# battery_cell.net
KiCad netlist of a schematic drawn in Altium Designer
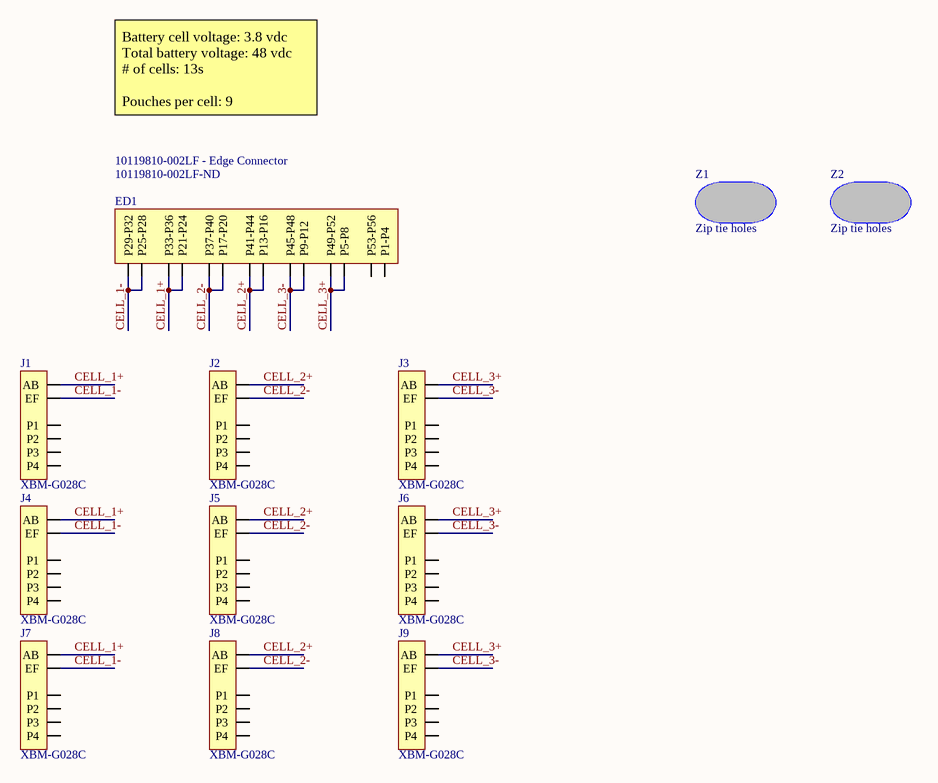
[diagram p0: battery_cell.SchDoc]

(export (version "E")
  (design (tool "Eeschema 10.0.6"))
  (components
    (comp (ref "ED1")
      (value "10119810-002LF - Edge Connector")
      (footprint "10119810-002LF - Edge Connector")
      (fields (field (name "SUPPLIER PART NUMBER 1") "10119810-002LF-ND"))
      (libsource (lib "bms") (part "10119810-002LF - Edge Connector"))
    )
    (comp (ref "J1")
      (value "XBM-G028C")
      (footprint "XBM-G028A")
      (description "28 pos power connector  (0.8X1.6mm pitch)-with post")
      (fields (field (name "MANUFACTURER") "Neoconix"))
      (libsource (lib "bms") (part "XBM-G028C"))
    )
    (comp (ref "J2")
      (value "XBM-G028C")
      (footprint "XBM-G028A")
      (description "28 pos power connector  (0.8X1.6mm pitch)-with post")
      (fields (field (name "MANUFACTURER") "Neoconix"))
      (libsource (lib "bms") (part "XBM-G028C"))
    )
    (comp (ref "J3")
      (value "XBM-G028C")
      (footprint "XBM-G028A")
      (description "28 pos power connector  (0.8X1.6mm pitch)-with post")
      (fields (field (name "MANUFACTURER") "Neoconix"))
      (libsource (lib "bms") (part "XBM-G028C"))
    )
    (comp (ref "J4")
      (value "XBM-G028C")
      (footprint "XBM-G028A")
      (description "28 pos power connector  (0.8X1.6mm pitch)-with post")
      (fields (field (name "MANUFACTURER") "Neoconix"))
      (libsource (lib "bms") (part "XBM-G028C"))
    )
    (comp (ref "J5")
      (value "XBM-G028C")
      (footprint "XBM-G028A")
      (description "28 pos power connector  (0.8X1.6mm pitch)-with post")
      (fields (field (name "MANUFACTURER") "Neoconix"))
      (libsource (lib "bms") (part "XBM-G028C"))
    )
    (comp (ref "J6")
      (value "XBM-G028C")
      (footprint "XBM-G028A")
      (description "28 pos power connector  (0.8X1.6mm pitch)-with post")
      (fields (field (name "MANUFACTURER") "Neoconix"))
      (libsource (lib "bms") (part "XBM-G028C"))
    )
    (comp (ref "J7")
      (value "XBM-G028C")
      (footprint "XBM-G028A")
      (description "28 pos power connector  (0.8X1.6mm pitch)-with post")
      (fields (field (name "MANUFACTURER") "Neoconix"))
      (libsource (lib "bms") (part "XBM-G028C"))
    )
    (comp (ref "J8")
      (value "XBM-G028C")
      (footprint "XBM-G028A")
      (description "28 pos power connector  (0.8X1.6mm pitch)-with post")
      (fields (field (name "MANUFACTURER") "Neoconix"))
      (libsource (lib "bms") (part "XBM-G028C"))
    )
    (comp (ref "J9")
      (value "XBM-G028C")
      (footprint "XBM-G028A")
      (description "28 pos power connector  (0.8X1.6mm pitch)-with post")
      (fields (field (name "MANUFACTURER") "Neoconix"))
      (libsource (lib "bms") (part "XBM-G028C"))
    )
    (comp (ref "Z1")
      (value "Zip tie holes")
      (footprint "ZIP_TIE_HOLE")
      (libsource (lib "bms") (part "ZIP_TIE_HOLE"))
    )
    (comp (ref "Z2")
      (value "Zip tie holes")
      (footprint "ZIP_TIE_HOLE")
      (libsource (lib "bms") (part "ZIP_TIE_HOLE"))
    )
  )
  (nets
    (net (code "1") (name "/CELL_1+") (class "Default")
      (node (ref "ED1") (pin "P21-P24") (pinfunction "P21-P24_P21-P24") (pintype "power_in"))
      (node (ref "ED1") (pin "P33-P36") (pinfunction "P33-P36_P33-P36") (pintype "power_in"))
      (node (ref "J1") (pin "AB") (pinfunction "AB_AB") (pintype "power_in"))
      (node (ref "J4") (pin "AB") (pinfunction "AB_AB") (pintype "power_in"))
      (node (ref "J7") (pin "AB") (pinfunction "AB_AB") (pintype "power_in"))
    )
    (net (code "2") (name "/CELL_1-") (class "Default")
      (node (ref "ED1") (pin "P25-P28") (pinfunction "P25-P28_P25-P28") (pintype "power_in"))
      (node (ref "ED1") (pin "P29-P32") (pinfunction "P29-P32_P29-P32") (pintype "power_in"))
      (node (ref "J1") (pin "EF") (pinfunction "EF_EF") (pintype "power_in"))
      (node (ref "J4") (pin "EF") (pinfunction "EF_EF") (pintype "power_in"))
      (node (ref "J7") (pin "EF") (pinfunction "EF_EF") (pintype "power_in"))
    )
    (net (code "3") (name "/CELL_2+") (class "Default")
      (node (ref "ED1") (pin "P13-P16") (pinfunction "P13-P16_P13-P16") (pintype "power_in"))
      (node (ref "ED1") (pin "P41-P44") (pinfunction "P41-P44_P41-P44") (pintype "power_in"))
      (node (ref "J2") (pin "AB") (pinfunction "AB_AB") (pintype "power_in"))
      (node (ref "J5") (pin "AB") (pinfunction "AB_AB") (pintype "power_in"))
      (node (ref "J8") (pin "AB") (pinfunction "AB_AB") (pintype "power_in"))
    )
    (net (code "4") (name "/CELL_2-") (class "Default")
      (node (ref "ED1") (pin "P17-P20") (pinfunction "P17-P20_P17-P20") (pintype "power_in"))
      (node (ref "ED1") (pin "P37-P40") (pinfunction "P37-P40_P37-P40") (pintype "power_in"))
      (node (ref "J2") (pin "EF") (pinfunction "EF_EF") (pintype "power_in"))
      (node (ref "J5") (pin "EF") (pinfunction "EF_EF") (pintype "power_in"))
      (node (ref "J8") (pin "EF") (pinfunction "EF_EF") (pintype "power_in"))
    )
    (net (code "5") (name "/CELL_3+") (class "Default")
      (node (ref "ED1") (pin "P49-P52") (pinfunction "P49-P52_P49-P52") (pintype "power_in"))
      (node (ref "ED1") (pin "P5-P8") (pinfunction "P5-P8_P5-P8") (pintype "power_in"))
      (node (ref "J3") (pin "AB") (pinfunction "AB_AB") (pintype "power_in"))
      (node (ref "J6") (pin "AB") (pinfunction "AB_AB") (pintype "power_in"))
      (node (ref "J9") (pin "AB") (pinfunction "AB_AB") (pintype "power_in"))
    )
    (net (code "6") (name "/CELL_3-") (class "Default")
      (node (ref "ED1") (pin "P45-P48") (pinfunction "P45-P48_P45-P48") (pintype "power_in"))
      (node (ref "ED1") (pin "P9-P12") (pinfunction "P9-P12_P9-P12") (pintype "power_in"))
      (node (ref "J3") (pin "EF") (pinfunction "EF_EF") (pintype "power_in"))
      (node (ref "J6") (pin "EF") (pinfunction "EF_EF") (pintype "power_in"))
      (node (ref "J9") (pin "EF") (pinfunction "EF_EF") (pintype "power_in"))
    )
    (net (code "7") (name "unconnected-(ED1-PadP1-P4)") (class "Default")
      (node (ref "ED1") (pin "P1-P4") (pinfunction "P1-P4_P1-P4") (pintype "power_in"))
    )
    (net (code "8") (name "unconnected-(ED1-PadP53-P56)") (class "Default")
      (node (ref "ED1") (pin "P53-P56") (pinfunction "P53-P56_P53-P56") (pintype "power_in"))
    )
    (net (code "9") (name "unconnected-(J1-PadP1)") (class "Default")
      (node (ref "J1") (pin "P1") (pinfunction "P1_P1") (pintype "passive"))
    )
    (net (code "10") (name "unconnected-(J1-PadP2)") (class "Default")
      (node (ref "J1") (pin "P2") (pinfunction "P2_P2") (pintype "passive"))
    )
    (net (code "11") (name "unconnected-(J1-PadP3)") (class "Default")
      (node (ref "J1") (pin "P3") (pinfunction "P3_P3") (pintype "passive"))
    )
    (net (code "12") (name "unconnected-(J1-PadP4)") (class "Default")
      (node (ref "J1") (pin "P4") (pinfunction "P4_P4") (pintype "passive"))
    )
    (net (code "13") (name "unconnected-(J2-PadP1)") (class "Default")
      (node (ref "J2") (pin "P1") (pinfunction "P1_P1") (pintype "passive"))
    )
    (net (code "14") (name "unconnected-(J2-PadP2)") (class "Default")
      (node (ref "J2") (pin "P2") (pinfunction "P2_P2") (pintype "passive"))
    )
    (net (code "15") (name "unconnected-(J2-PadP3)") (class "Default")
      (node (ref "J2") (pin "P3") (pinfunction "P3_P3") (pintype "passive"))
    )
    (net (code "16") (name "unconnected-(J2-PadP4)") (class "Default")
      (node (ref "J2") (pin "P4") (pinfunction "P4_P4") (pintype "passive"))
    )
    (net (code "17") (name "unconnected-(J3-PadP1)") (class "Default")
      (node (ref "J3") (pin "P1") (pinfunction "P1_P1") (pintype "passive"))
    )
    (net (code "18") (name "unconnected-(J3-PadP2)") (class "Default")
      (node (ref "J3") (pin "P2") (pinfunction "P2_P2") (pintype "passive"))
    )
    (net (code "19") (name "unconnected-(J3-PadP3)") (class "Default")
      (node (ref "J3") (pin "P3") (pinfunction "P3_P3") (pintype "passive"))
    )
    (net (code "20") (name "unconnected-(J3-PadP4)") (class "Default")
      (node (ref "J3") (pin "P4") (pinfunction "P4_P4") (pintype "passive"))
    )
    (net (code "21") (name "unconnected-(J4-PadP1)") (class "Default")
      (node (ref "J4") (pin "P1") (pinfunction "P1_P1") (pintype "passive"))
    )
    (net (code "22") (name "unconnected-(J4-PadP2)") (class "Default")
      (node (ref "J4") (pin "P2") (pinfunction "P2_P2") (pintype "passive"))
    )
    (net (code "23") (name "unconnected-(J4-PadP3)") (class "Default")
      (node (ref "J4") (pin "P3") (pinfunction "P3_P3") (pintype "passive"))
    )
    (net (code "24") (name "unconnected-(J4-PadP4)") (class "Default")
      (node (ref "J4") (pin "P4") (pinfunction "P4_P4") (pintype "passive"))
    )
    (net (code "25") (name "unconnected-(J5-PadP1)") (class "Default")
      (node (ref "J5") (pin "P1") (pinfunction "P1_P1") (pintype "passive"))
    )
    (net (code "26") (name "unconnected-(J5-PadP2)") (class "Default")
      (node (ref "J5") (pin "P2") (pinfunction "P2_P2") (pintype "passive"))
    )
    (net (code "27") (name "unconnected-(J5-PadP3)") (class "Default")
      (node (ref "J5") (pin "P3") (pinfunction "P3_P3") (pintype "passive"))
    )
    (net (code "28") (name "unconnected-(J5-PadP4)") (class "Default")
      (node (ref "J5") (pin "P4") (pinfunction "P4_P4") (pintype "passive"))
    )
    (net (code "29") (name "unconnected-(J6-PadP1)") (class "Default")
      (node (ref "J6") (pin "P1") (pinfunction "P1_P1") (pintype "passive"))
    )
    (net (code "30") (name "unconnected-(J6-PadP2)") (class "Default")
      (node (ref "J6") (pin "P2") (pinfunction "P2_P2") (pintype "passive"))
    )
    (net (code "31") (name "unconnected-(J6-PadP3)") (class "Default")
      (node (ref "J6") (pin "P3") (pinfunction "P3_P3") (pintype "passive"))
    )
    (net (code "32") (name "unconnected-(J6-PadP4)") (class "Default")
      (node (ref "J6") (pin "P4") (pinfunction "P4_P4") (pintype "passive"))
    )
    (net (code "33") (name "unconnected-(J7-PadP1)") (class "Default")
      (node (ref "J7") (pin "P1") (pinfunction "P1_P1") (pintype "passive"))
    )
    (net (code "34") (name "unconnected-(J7-PadP2)") (class "Default")
      (node (ref "J7") (pin "P2") (pinfunction "P2_P2") (pintype "passive"))
    )
    (net (code "35") (name "unconnected-(J7-PadP3)") (class "Default")
      (node (ref "J7") (pin "P3") (pinfunction "P3_P3") (pintype "passive"))
    )
    (net (code "36") (name "unconnected-(J7-PadP4)") (class "Default")
      (node (ref "J7") (pin "P4") (pinfunction "P4_P4") (pintype "passive"))
    )
    (net (code "37") (name "unconnected-(J8-PadP1)") (class "Default")
      (node (ref "J8") (pin "P1") (pinfunction "P1_P1") (pintype "passive"))
    )
    (net (code "38") (name "unconnected-(J8-PadP2)") (class "Default")
      (node (ref "J8") (pin "P2") (pinfunction "P2_P2") (pintype "passive"))
    )
    (net (code "39") (name "unconnected-(J8-PadP3)") (class "Default")
      (node (ref "J8") (pin "P3") (pinfunction "P3_P3") (pintype "passive"))
    )
    (net (code "40") (name "unconnected-(J8-PadP4)") (class "Default")
      (node (ref "J8") (pin "P4") (pinfunction "P4_P4") (pintype "passive"))
    )
    (net (code "41") (name "unconnected-(J9-PadP1)") (class "Default")
      (node (ref "J9") (pin "P1") (pinfunction "P1_P1") (pintype "passive"))
    )
    (net (code "42") (name "unconnected-(J9-PadP2)") (class "Default")
      (node (ref "J9") (pin "P2") (pinfunction "P2_P2") (pintype "passive"))
    )
    (net (code "43") (name "unconnected-(J9-PadP3)") (class "Default")
      (node (ref "J9") (pin "P3") (pinfunction "P3_P3") (pintype "passive"))
    )
    (net (code "44") (name "unconnected-(J9-PadP4)") (class "Default")
      (node (ref "J9") (pin "P4") (pinfunction "P4_P4") (pintype "passive"))
    )
  )
)
